# Pure_ADSR.net
KiCad netlist of a schematic drawn in EAGLE
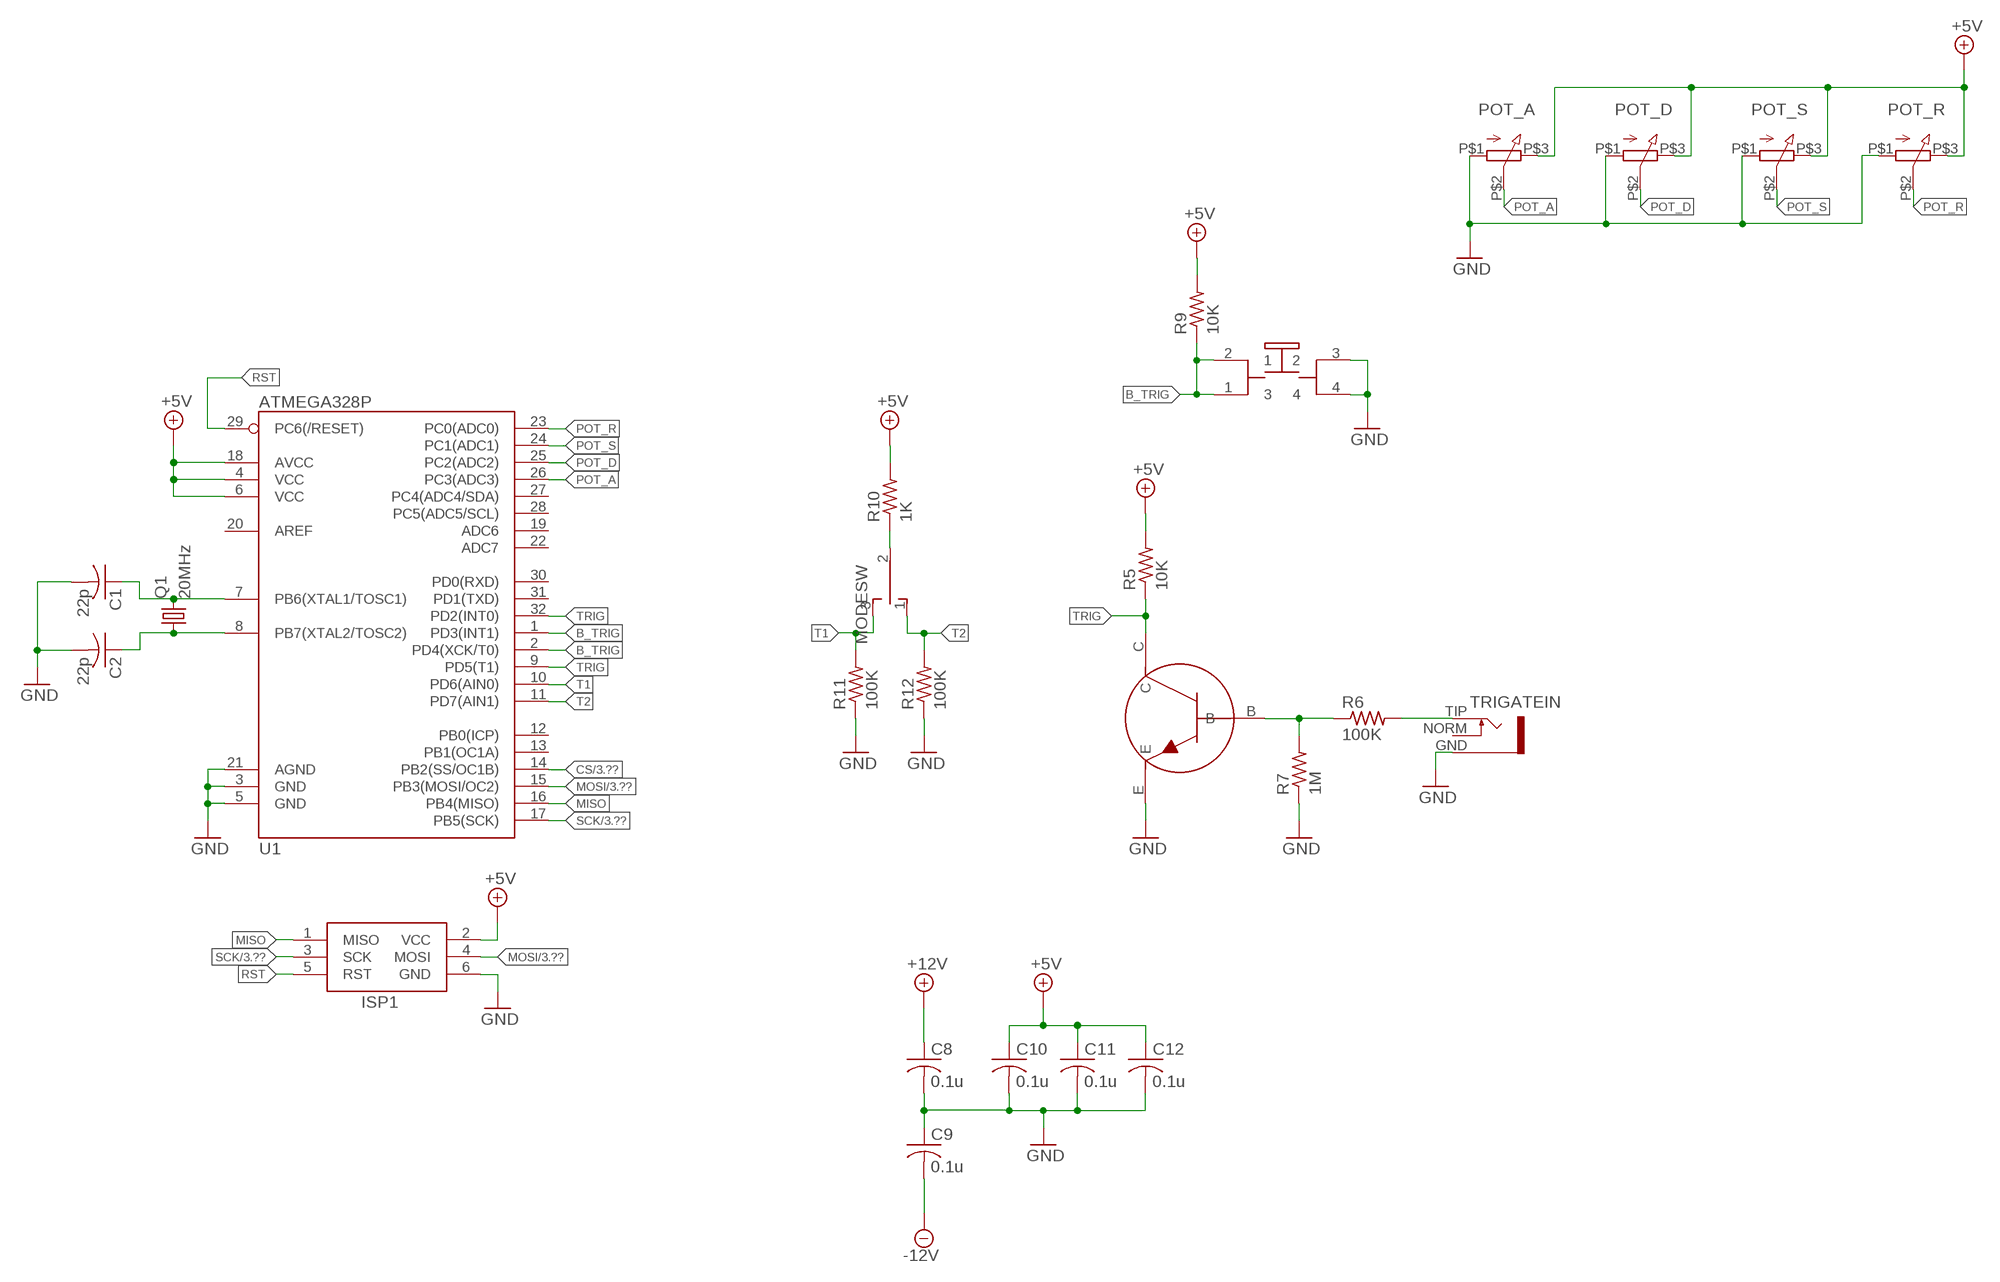
[diagram p0: schematic, sheet 1]
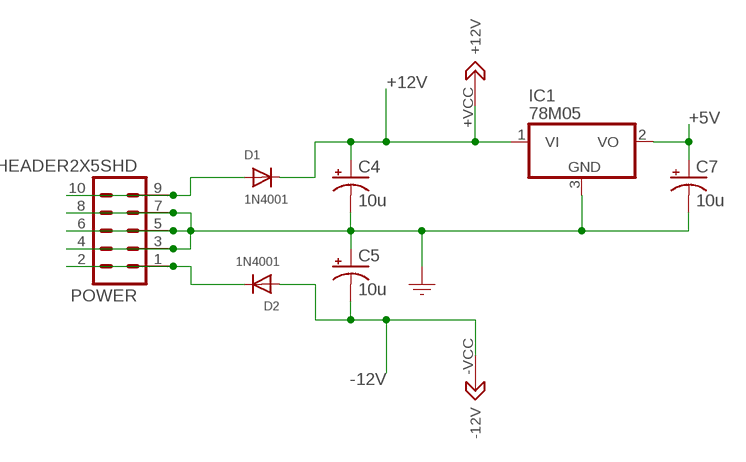
[diagram p1: schematic, sheet 2]
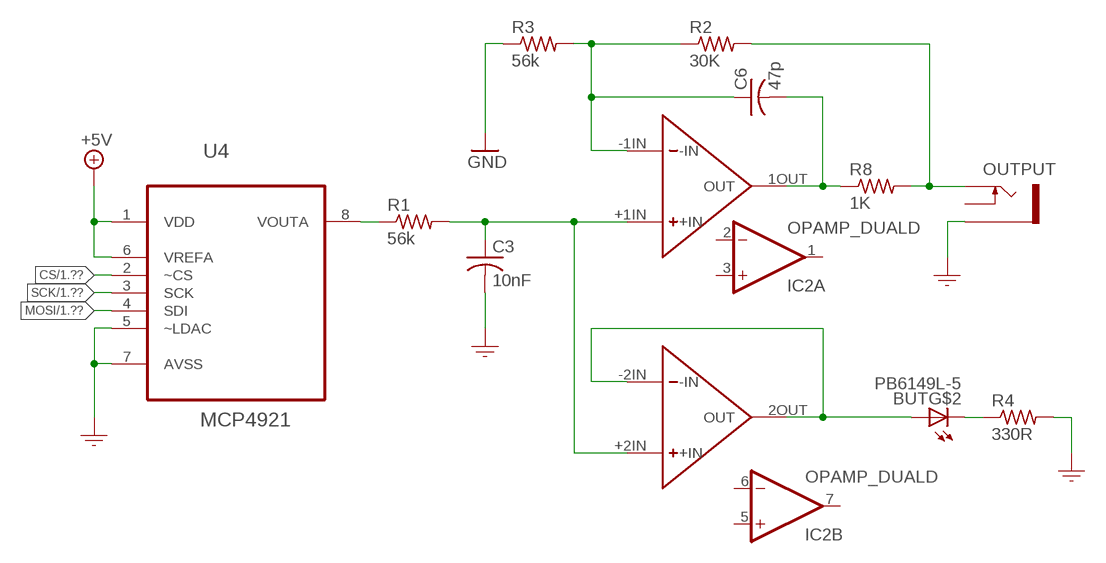
[diagram p2: schematic, sheet 3]

(export (version "E")
  (design (tool "Eeschema 10.0.6"))
  (components
    (comp (ref "C4")
      (value "10u")
      (footprint "eagle-import:153CLV-0505")
      (libsource (lib "eagle-import") (part "CAPACITOR_POL-US153CLV-0505"))
    )
    (comp (ref "C5")
      (value "10u")
      (footprint "eagle-import:153CLV-0505")
      (libsource (lib "eagle-import") (part "CAPACITOR_POL-US153CLV-0505"))
    )
    (comp (ref "C7")
      (value "10u")
      (footprint "eagle-import:153CLV-0505")
      (libsource (lib "eagle-import") (part "CAPACITOR_POL-US153CLV-0505"))
    )
    (comp (ref "D1")
      (value "1N4001")
      (footprint "eagle-import:SMADIODE")
      (libsource (lib "eagle-import") (part "DIODESMA"))
    )
    (comp (ref "D2")
      (value "1N4001")
      (footprint "eagle-import:SMADIODE")
      (libsource (lib "eagle-import") (part "DIODESMA"))
    )
    (comp (ref "IC1")
      (value "78M05")
      (footprint "eagle-import:TO252")
      (libsource (lib "eagle-import") (part "VOLTAGE_REG_POSDT05"))
    )
    (comp (ref "POWER")
      (value "HEADER2X5SHD")
      (footprint "eagle-import:2X5-SHROUDED")
      (libsource (lib "eagle-import") (part "HEADER2X5SHD"))
    )
    (comp (ref "U2")
      (value "DUAL_OPAMP")
      (footprint "eagle-import:DUAL_OPAMP")
      (libsource (lib "eagle-import") (part "DUAL_OPAMP"))
    )
    (comp (ref "BUT")
      (value "PB6149L-5")
      (footprint "eagle-import:PB6149L")
      (libsource (lib "eagle-import") (part "SWITCH_PUSHBUTTON_LED"))
    )
    (comp (ref "C3")
      (value "10nF")
      (footprint "eagle-import:C0805")
      (libsource (lib "eagle-import") (part "CAPACITOR-USC0805"))
    )
    (comp (ref "C6")
      (value "47p")
      (footprint "eagle-import:C0805")
      (libsource (lib "eagle-import") (part "CAPACITOR-USC0805"))
    )
    (comp (ref "IC2")
      (value "OPAMP_DUALD")
      (footprint "eagle-import:SO08")
      (libsource (lib "eagle-import") (part "OPAMP_DUALD"))
    )
    (comp (ref "OUTPUT")
      (value "SOCKET_MONO_3.5MMPJ301M-12")
      (footprint "eagle-import:PJ301M-12")
      (libsource (lib "eagle-import") (part "SOCKET_MONO_3.5MMPJ301M-12"))
    )
    (comp (ref "R1")
      (value "56k")
      (footprint "eagle-import:R0805")
      (libsource (lib "eagle-import") (part "RESISTOR_USR0805"))
    )
    (comp (ref "R2")
      (value "30K")
      (footprint "eagle-import:R0805")
      (libsource (lib "eagle-import") (part "RESISTOR_USR0805"))
    )
    (comp (ref "R3")
      (value "56k")
      (footprint "eagle-import:R0805")
      (libsource (lib "eagle-import") (part "RESISTOR_USR0805"))
    )
    (comp (ref "R4")
      (value "330R")
      (footprint "eagle-import:R0805")
      (libsource (lib "eagle-import") (part "RESISTOR_USR0805"))
    )
    (comp (ref "R8")
      (value "1K")
      (footprint "eagle-import:R0805")
      (libsource (lib "eagle-import") (part "RESISTOR_USR0805"))
    )
    (comp (ref "U4")
      (value "MCP4921")
      (footprint "eagle-import:SOIC8")
      (libsource (lib "eagle-import") (part "DAC_SINGLE_12B_MCP4921"))
    )
    (comp (ref "C1")
      (value "22p")
      (footprint "eagle-import:C0805K")
      (libsource (lib "eagle-import") (part "C-USC0805K"))
    )
    (comp (ref "C2")
      (value "22p")
      (footprint "eagle-import:C0805K")
      (libsource (lib "eagle-import") (part "C-USC0805K"))
    )
    (comp (ref "C8")
      (value "0.1u")
      (footprint "eagle-import:C0805K")
      (libsource (lib "eagle-import") (part "C-USC0805K"))
    )
    (comp (ref "C9")
      (value "0.1u")
      (footprint "eagle-import:C0805K")
      (libsource (lib "eagle-import") (part "C-USC0805K"))
    )
    (comp (ref "C10")
      (value "0.1u")
      (footprint "eagle-import:C0805K")
      (libsource (lib "eagle-import") (part "C-USC0805K"))
    )
    (comp (ref "C11")
      (value "0.1u")
      (footprint "eagle-import:C0805K")
      (libsource (lib "eagle-import") (part "C-USC0805K"))
    )
    (comp (ref "C12")
      (value "0.1u")
      (footprint "eagle-import:C0805K")
      (libsource (lib "eagle-import") (part "C-USC0805K"))
    )
    (comp (ref "ISP1")
      (value "AVRISP-6")
      (footprint "eagle-import:AVRISP")
      (libsource (lib "eagle-import") (part "AVRISP-6"))
    )
    (comp (ref "MODESW")
      (value "TOGGLE_ON_OFF_ON")
      (footprint "eagle-import:TOGGLE_ON_OFF_ON")
      (libsource (lib "eagle-import") (part "TOGGLE_ON_OFF_ON"))
    )
    (comp (ref "POT_A")
      (value "Q-POT")
      (footprint "eagle-import:Q-POT")
      (libsource (lib "eagle-import") (part "Q-POT"))
    )
    (comp (ref "POT_D")
      (value "Q-POT")
      (footprint "eagle-import:Q-POT")
      (libsource (lib "eagle-import") (part "Q-POT"))
    )
    (comp (ref "POT_R")
      (value "Q-POT")
      (footprint "eagle-import:Q-POT")
      (libsource (lib "eagle-import") (part "Q-POT"))
    )
    (comp (ref "POT_S")
      (value "Q-POT")
      (footprint "eagle-import:Q-POT")
      (libsource (lib "eagle-import") (part "Q-POT"))
    )
    (comp (ref "Q1")
      (value "20MHz")
      (footprint "eagle-import:HC49UP")
      (libsource (lib "eagle-import") (part "CRYSTALHC49UP"))
    )
    (comp (ref "R5")
      (value "10K")
      (footprint "eagle-import:R0805")
      (libsource (lib "eagle-import") (part "R-US_R0805"))
    )
    (comp (ref "R6")
      (value "100K")
      (footprint "eagle-import:R0805")
      (libsource (lib "eagle-import") (part "R-US_R0805"))
    )
    (comp (ref "R7")
      (value "1M")
      (footprint "eagle-import:R0805")
      (libsource (lib "eagle-import") (part "R-US_R0805"))
    )
    (comp (ref "R9")
      (value "10K")
      (footprint "eagle-import:R0805")
      (libsource (lib "eagle-import") (part "R-US_R0805"))
    )
    (comp (ref "R10")
      (value "1K")
      (footprint "eagle-import:R0805")
      (libsource (lib "eagle-import") (part "R-US_R0805"))
    )
    (comp (ref "R11")
      (value "100K")
      (footprint "eagle-import:R0805")
      (libsource (lib "eagle-import") (part "R-US_R0805"))
    )
    (comp (ref "R12")
      (value "100K")
      (footprint "eagle-import:R0805")
      (libsource (lib "eagle-import") (part "R-US_R0805"))
    )
    (comp (ref "T1")
      (value "2N3904")
      (footprint "eagle-import:TRANSISTOR_SINGLE_N-TYPE")
      (libsource (lib "eagle-import") (part "TRANSISTOR_MMBT3904"))
    )
    (comp (ref "TRIGATEIN")
      (value "S_JACK")
      (footprint "eagle-import:S_JACK")
      (libsource (lib "eagle-import") (part "S_JACK"))
    )
    (comp (ref "U1")
      (value "ATMEGA328P")
      (footprint "eagle-import:TQFP32-08")
      (libsource (lib "eagle-import") (part "ATMEGA328_SMT"))
    )
  )
  (nets
    (net (code "1") (name "+5V") (class "Default")
      (node (ref "C10") (pin "1") (pinfunction "1_1") (pintype "passive"))
      (node (ref "C11") (pin "1") (pinfunction "1_1") (pintype "passive"))
      (node (ref "C12") (pin "1") (pinfunction "1_1") (pintype "passive"))
      (node (ref "C7") (pin "+") (pinfunction "+_+") (pintype "passive"))
      (node (ref "IC1") (pin "2") (pinfunction "VO_2") (pintype "passive"))
      (node (ref "ISP1") (pin "2") (pinfunction "VCC_2") (pintype "power_in"))
      (node (ref "POT_A") (pin "P$3") (pinfunction "3_P$3") (pintype "passive"))
      (node (ref "POT_D") (pin "P$3") (pinfunction "3_P$3") (pintype "passive"))
      (node (ref "POT_R") (pin "P$3") (pinfunction "3_P$3") (pintype "passive"))
      (node (ref "POT_S") (pin "P$3") (pinfunction "3_P$3") (pintype "passive"))
      (node (ref "R10") (pin "2") (pinfunction "2_2") (pintype "passive"))
      (node (ref "R5") (pin "2") (pinfunction "2_2") (pintype "passive"))
      (node (ref "R9") (pin "2") (pinfunction "2_2") (pintype "passive"))
      (node (ref "U1") (pin "18") (pinfunction "AVCC_18") (pintype "bidirectional"))
      (node (ref "U1") (pin "4") (pinfunction "VCC_4") (pintype "bidirectional"))
      (node (ref "U1") (pin "6") (pinfunction "VCC_6") (pintype "bidirectional"))
      (node (ref "U4") (pin "1") (pinfunction "VDD_1") (pintype "power_in"))
      (node (ref "U4") (pin "6") (pinfunction "VREFA_6") (pintype "input"))
    )
    (net (code "2") (name "+12V") (class "Default")
      (node (ref "C4") (pin "+") (pinfunction "+_+") (pintype "passive"))
      (node (ref "C8") (pin "1") (pinfunction "1_1") (pintype "passive"))
      (node (ref "D1") (pin "C") (pinfunction "C_C") (pintype "passive"))
      (node (ref "IC1") (pin "1") (pinfunction "VI_1") (pintype "input"))
      (node (ref "U2") (pin "+VCC") (pinfunction "+12V_+VCC") (pintype "bidirectional"))
    )
    (net (code "3") (name "-12V") (class "Default")
      (node (ref "C5") (pin "-") (pinfunction "-_-") (pintype "passive"))
      (node (ref "C9") (pin "2") (pinfunction "2_2") (pintype "passive"))
      (node (ref "D2") (pin "A") (pinfunction "A_A") (pintype "passive"))
      (node (ref "U2") (pin "-VCC") (pinfunction "-12V_-VCC") (pintype "bidirectional"))
    )
    (net (code "4") (name "B_TRIG") (class "Default")
      (node (ref "BUT") (pin "1") (pinfunction "3_1") (pintype "bidirectional"))
      (node (ref "BUT") (pin "2") (pinfunction "1_2") (pintype "bidirectional"))
      (node (ref "R9") (pin "1") (pinfunction "1_1") (pintype "passive"))
      (node (ref "U1") (pin "1") (pinfunction "PD3(INT1)_1") (pintype "bidirectional"))
      (node (ref "U1") (pin "2") (pinfunction "PD4(XCK/T0)_2") (pintype "bidirectional"))
    )
    (net (code "5") (name "CS") (class "Default")
      (node (ref "U1") (pin "14") (pinfunction "PB2(SS/OC1B)_14") (pintype "bidirectional"))
      (node (ref "U4") (pin "2") (pinfunction "~{CS}_2") (pintype "input"))
    )
    (net (code "6") (name "GND") (class "Default")
      (node (ref "BUT") (pin "3") (pinfunction "2_3") (pintype "bidirectional"))
      (node (ref "BUT") (pin "4") (pinfunction "4_4") (pintype "bidirectional"))
      (node (ref "C1") (pin "2") (pinfunction "2_2") (pintype "passive"))
      (node (ref "C10") (pin "2") (pinfunction "2_2") (pintype "passive"))
      (node (ref "C11") (pin "2") (pinfunction "2_2") (pintype "passive"))
      (node (ref "C12") (pin "2") (pinfunction "2_2") (pintype "passive"))
      (node (ref "C2") (pin "2") (pinfunction "2_2") (pintype "passive"))
      (node (ref "C3") (pin "2") (pinfunction "2_2") (pintype "passive"))
      (node (ref "C4") (pin "-") (pinfunction "-_-") (pintype "passive"))
      (node (ref "C5") (pin "+") (pinfunction "+_+") (pintype "passive"))
      (node (ref "C7") (pin "-") (pinfunction "-_-") (pintype "passive"))
      (node (ref "C8") (pin "2") (pinfunction "2_2") (pintype "passive"))
      (node (ref "C9") (pin "1") (pinfunction "1_1") (pintype "passive"))
      (node (ref "IC1") (pin "3") (pinfunction "GND_3") (pintype "passive"))
      (node (ref "ISP1") (pin "6") (pinfunction "GND_6") (pintype "power_in"))
      (node (ref "OUTPUT") (pin "GND") (pinfunction "SLEEVE_GND") (pintype "passive"))
      (node (ref "POT_A") (pin "P$1") (pinfunction "1_P$1") (pintype "passive"))
      (node (ref "POT_D") (pin "P$1") (pinfunction "1_P$1") (pintype "passive"))
      (node (ref "POT_R") (pin "P$1") (pinfunction "1_P$1") (pintype "passive"))
      (node (ref "POT_S") (pin "P$1") (pinfunction "1_P$1") (pintype "passive"))
      (node (ref "POWER") (pin "3") (pinfunction "3_3") (pintype "passive"))
      (node (ref "POWER") (pin "4") (pinfunction "4_4") (pintype "passive"))
      (node (ref "POWER") (pin "5") (pinfunction "5_5") (pintype "passive"))
      (node (ref "POWER") (pin "6") (pinfunction "6_6") (pintype "passive"))
      (node (ref "POWER") (pin "7") (pinfunction "7_7") (pintype "passive"))
      (node (ref "POWER") (pin "8") (pinfunction "8_8") (pintype "passive"))
      (node (ref "R11") (pin "1") (pinfunction "1_1") (pintype "passive"))
      (node (ref "R12") (pin "1") (pinfunction "1_1") (pintype "passive"))
      (node (ref "R3") (pin "1") (pinfunction "1_1") (pintype "passive"))
      (node (ref "R4") (pin "2") (pinfunction "2_2") (pintype "passive"))
      (node (ref "R7") (pin "1") (pinfunction "1_1") (pintype "passive"))
      (node (ref "T1") (pin "E") (pinfunction "E_E") (pintype "bidirectional"))
      (node (ref "TRIGATEIN") (pin "GND") (pinfunction "GND_GND") (pintype "passive"))
      (node (ref "U1") (pin "21") (pinfunction "AGND_21") (pintype "bidirectional"))
      (node (ref "U1") (pin "3") (pinfunction "GND_3") (pintype "bidirectional"))
      (node (ref "U1") (pin "5") (pinfunction "GND_5") (pintype "bidirectional"))
      (node (ref "U4") (pin "5") (pinfunction "~{LDAC}_5") (pintype "input"))
      (node (ref "U4") (pin "7") (pinfunction "AVSS_7") (pintype "passive"))
    )
    (net (code "7") (name "MISO") (class "Default")
      (node (ref "ISP1") (pin "1") (pinfunction "MISO_1") (pintype "input"))
      (node (ref "U1") (pin "16") (pinfunction "PB4(MISO)_16") (pintype "bidirectional"))
    )
    (net (code "8") (name "MOSI") (class "Default")
      (node (ref "ISP1") (pin "4") (pinfunction "MOSI_4") (pintype "output"))
      (node (ref "U1") (pin "15") (pinfunction "PB3(MOSI/OC2)_15") (pintype "bidirectional"))
      (node (ref "U4") (pin "4") (pinfunction "SDI_4") (pintype "input"))
    )
    (net (code "9") (name "Net-(BUTB-C)") (class "Default")
      (node (ref "BUT") (pin "K") (pinfunction "C_K") (pintype "passive"))
      (node (ref "R4") (pin "1") (pinfunction "1_1") (pintype "passive"))
    )
    (net (code "10") (name "Net-(D1-PadA)") (class "Default")
      (node (ref "D1") (pin "A") (pinfunction "A_A") (pintype "passive"))
      (node (ref "POWER") (pin "10") (pinfunction "10_10") (pintype "passive"))
      (node (ref "POWER") (pin "9") (pinfunction "9_9") (pintype "passive"))
    )
    (net (code "11") (name "Net-(D2-PadC)") (class "Default")
      (node (ref "D2") (pin "C") (pinfunction "C_C") (pintype "passive"))
      (node (ref "POWER") (pin "1") (pinfunction "1_1") (pintype "passive"))
      (node (ref "POWER") (pin "2") (pinfunction "2_2") (pintype "passive"))
    )
    (net (code "12") (name "Net-(MODESW-P)") (class "Default")
      (node (ref "MODESW") (pin "2") (pinfunction "P_2") (pintype "passive"))
      (node (ref "R10") (pin "1") (pinfunction "1_1") (pintype "passive"))
    )
    (net (code "13") (name "Net-(OUTPUT-PadTIP)") (class "Default")
      (node (ref "OUTPUT") (pin "TIP") (pinfunction "TIP_TIP") (pintype "passive"))
      (node (ref "R2") (pin "2") (pinfunction "2_2") (pintype "passive"))
      (node (ref "R8") (pin "2") (pinfunction "2_2") (pintype "passive"))
    )
    (net (code "14") (name "Net-(R6-Pad1)") (class "Default")
      (node (ref "R6") (pin "1") (pinfunction "1_1") (pintype "passive"))
      (node (ref "R7") (pin "2") (pinfunction "2_2") (pintype "passive"))
      (node (ref "T1") (pin "B") (pinfunction "B_B") (pintype "bidirectional"))
    )
    (net (code "15") (name "Net-(R6-Pad2)") (class "Default")
      (node (ref "R6") (pin "2") (pinfunction "2_2") (pintype "passive"))
      (node (ref "TRIGATEIN") (pin "TIP") (pinfunction "TIP_TIP") (pintype "passive"))
    )
    (net (code "16") (name "Net-(U1-PB6(XTAL1{slash}TOSC1))") (class "Default")
      (node (ref "C1") (pin "1") (pinfunction "1_1") (pintype "passive"))
      (node (ref "Q1") (pin "2") (pinfunction "2_2") (pintype "passive"))
      (node (ref "U1") (pin "7") (pinfunction "PB6(XTAL1/TOSC1)_7") (pintype "bidirectional"))
    )
    (net (code "17") (name "Net-(U1-PB7(XTAL2{slash}TOSC2))") (class "Default")
      (node (ref "C2") (pin "1") (pinfunction "1_1") (pintype "passive"))
      (node (ref "Q1") (pin "1") (pinfunction "1_1") (pintype "passive"))
      (node (ref "U1") (pin "8") (pinfunction "PB7(XTAL2/TOSC2)_8") (pintype "bidirectional"))
    )
    (net (code "18") (name "Net-(U2A-+IN)") (class "Default")
      (node (ref "C3") (pin "1") (pinfunction "1_1") (pintype "passive"))
      (node (ref "R1") (pin "2") (pinfunction "2_2") (pintype "passive"))
      (node (ref "U2") (pin "+1IN") (pinfunction "+IN_+1IN") (pintype "bidirectional"))
      (node (ref "U2") (pin "+2IN") (pinfunction "+IN_+2IN") (pintype "bidirectional"))
    )
    (net (code "19") (name "Net-(U2A--IN)") (class "Default")
      (node (ref "C6") (pin "1") (pinfunction "1_1") (pintype "passive"))
      (node (ref "R2") (pin "1") (pinfunction "1_1") (pintype "passive"))
      (node (ref "R3") (pin "2") (pinfunction "2_2") (pintype "passive"))
      (node (ref "U2") (pin "-1IN") (pinfunction "-IN_-1IN") (pintype "bidirectional"))
    )
    (net (code "20") (name "Net-(U2A-OUT)") (class "Default")
      (node (ref "C6") (pin "2") (pinfunction "2_2") (pintype "passive"))
      (node (ref "R8") (pin "1") (pinfunction "1_1") (pintype "passive"))
      (node (ref "U2") (pin "1OUT") (pinfunction "OUT_1OUT") (pintype "bidirectional"))
    )
    (net (code "21") (name "Net-(U2B--IN)") (class "Default")
      (node (ref "BUT") (pin "A") (pinfunction "A_A") (pintype "passive"))
      (node (ref "U2") (pin "-2IN") (pinfunction "-IN_-2IN") (pintype "bidirectional"))
      (node (ref "U2") (pin "2OUT") (pinfunction "OUT_2OUT") (pintype "bidirectional"))
    )
    (net (code "22") (name "Net-(U4-VOUTA)") (class "Default")
      (node (ref "R1") (pin "1") (pinfunction "1_1") (pintype "passive"))
      (node (ref "U4") (pin "8") (pinfunction "VOUTA_8") (pintype "output"))
    )
    (net (code "23") (name "POT_A") (class "Default")
      (node (ref "POT_A") (pin "P$2") (pinfunction "2_P$2") (pintype "passive"))
      (node (ref "U1") (pin "26") (pinfunction "PC3(ADC3)_26") (pintype "bidirectional"))
    )
    (net (code "24") (name "POT_D") (class "Default")
      (node (ref "POT_D") (pin "P$2") (pinfunction "2_P$2") (pintype "passive"))
      (node (ref "U1") (pin "25") (pinfunction "PC2(ADC2)_25") (pintype "bidirectional"))
    )
    (net (code "25") (name "POT_R") (class "Default")
      (node (ref "POT_R") (pin "P$2") (pinfunction "2_P$2") (pintype "passive"))
      (node (ref "U1") (pin "23") (pinfunction "PC0(ADC0)_23") (pintype "bidirectional"))
    )
    (net (code "26") (name "POT_S") (class "Default")
      (node (ref "POT_S") (pin "P$2") (pinfunction "2_P$2") (pintype "passive"))
      (node (ref "U1") (pin "24") (pinfunction "PC1(ADC1)_24") (pintype "bidirectional"))
    )
    (net (code "27") (name "RST") (class "Default")
      (node (ref "ISP1") (pin "5") (pinfunction "RST_5") (pintype "output"))
      (node (ref "U1") (pin "29") (pinfunction "PC6(/RESET)_29") (pintype "bidirectional"))
    )
    (net (code "28") (name "SCK") (class "Default")
      (node (ref "ISP1") (pin "3") (pinfunction "SCK_3") (pintype "output"))
      (node (ref "U1") (pin "17") (pinfunction "PB5(SCK)_17") (pintype "bidirectional"))
      (node (ref "U4") (pin "3") (pinfunction "SCK_3") (pintype "input"))
    )
    (net (code "29") (name "T1") (class "Default")
      (node (ref "MODESW") (pin "3") (pinfunction "S_3") (pintype "passive"))
      (node (ref "R11") (pin "2") (pinfunction "2_2") (pintype "passive"))
      (node (ref "U1") (pin "10") (pinfunction "PD6(AIN0)_10") (pintype "bidirectional"))
    )
    (net (code "30") (name "T2") (class "Default")
      (node (ref "MODESW") (pin "1") (pinfunction "O_1") (pintype "passive"))
      (node (ref "R12") (pin "2") (pinfunction "2_2") (pintype "passive"))
      (node (ref "U1") (pin "11") (pinfunction "PD7(AIN1)_11") (pintype "bidirectional"))
    )
    (net (code "31") (name "TRIG") (class "Default")
      (node (ref "R5") (pin "1") (pinfunction "1_1") (pintype "passive"))
      (node (ref "T1") (pin "C") (pinfunction "C_C") (pintype "bidirectional"))
      (node (ref "U1") (pin "32") (pinfunction "PD2(INT0)_32") (pintype "bidirectional"))
      (node (ref "U1") (pin "9") (pinfunction "PD5(T1)_9") (pintype "bidirectional"))
    )
    (net (code "32") (name "unconnected-(IC2A-+IN-Pad3)") (class "Default")
      (node (ref "IC2") (pin "3") (pinfunction "+IN_3") (pintype "input"))
    )
    (net (code "33") (name "unconnected-(IC2A--IN-Pad2)") (class "Default")
      (node (ref "IC2") (pin "2") (pinfunction "-IN_2") (pintype "input"))
    )
    (net (code "34") (name "unconnected-(IC2A-OUT-Pad1)") (class "Default")
      (node (ref "IC2") (pin "1") (pinfunction "OUT_1") (pintype "output"))
    )
    (net (code "35") (name "unconnected-(IC2B-+IN-Pad5)") (class "Default")
      (node (ref "IC2") (pin "5") (pinfunction "+IN_5") (pintype "input"))
    )
    (net (code "36") (name "unconnected-(IC2B--IN-Pad6)") (class "Default")
      (node (ref "IC2") (pin "6") (pinfunction "-IN_6") (pintype "input"))
    )
    (net (code "37") (name "unconnected-(IC2B-OUT-Pad7)") (class "Default")
      (node (ref "IC2") (pin "7") (pinfunction "OUT_7") (pintype "output"))
    )
    (net (code "38") (name "unconnected-(OUTPUT-SWITCH-PadNORM)") (class "Default")
      (node (ref "OUTPUT") (pin "NORM") (pinfunction "SWITCH_NORM") (pintype "passive"))
    )
    (net (code "39") (name "unconnected-(TRIGATEIN-PadNORM)") (class "Default")
      (node (ref "TRIGATEIN") (pin "NORM") (pinfunction "NORM_NORM") (pintype "passive"))
    )
    (net (code "40") (name "unconnected-(U1-ADC6-Pad19)") (class "Default")
      (node (ref "U1") (pin "19") (pinfunction "ADC6_19") (pintype "bidirectional"))
    )
    (net (code "41") (name "unconnected-(U1-ADC7-Pad22)") (class "Default")
      (node (ref "U1") (pin "22") (pinfunction "ADC7_22") (pintype "bidirectional"))
    )
    (net (code "42") (name "unconnected-(U1-AREF-Pad20)") (class "Default")
      (node (ref "U1") (pin "20") (pinfunction "AREF_20") (pintype "bidirectional"))
    )
    (net (code "43") (name "unconnected-(U1-PB0(ICP)-Pad12)") (class "Default")
      (node (ref "U1") (pin "12") (pinfunction "PB0(ICP)_12") (pintype "bidirectional"))
    )
    (net (code "44") (name "unconnected-(U1-PB1(OC1A)-Pad13)") (class "Default")
      (node (ref "U1") (pin "13") (pinfunction "PB1(OC1A)_13") (pintype "bidirectional"))
    )
    (net (code "45") (name "unconnected-(U1-PC4(ADC4{slash}SDA)-Pad27)") (class "Default")
      (node (ref "U1") (pin "27") (pinfunction "PC4(ADC4/SDA)_27") (pintype "bidirectional"))
    )
    (net (code "46") (name "unconnected-(U1-PC5(ADC5{slash}SCL)-Pad28)") (class "Default")
      (node (ref "U1") (pin "28") (pinfunction "PC5(ADC5/SCL)_28") (pintype "bidirectional"))
    )
    (net (code "47") (name "unconnected-(U1-PD0(RXD)-Pad30)") (class "Default")
      (node (ref "U1") (pin "30") (pinfunction "PD0(RXD)_30") (pintype "bidirectional"))
    )
    (net (code "48") (name "unconnected-(U1-PD1(TXD)-Pad31)") (class "Default")
      (node (ref "U1") (pin "31") (pinfunction "PD1(TXD)_31") (pintype "bidirectional"))
    )
  )
)
